# croky_b_1_6_maxi.net
KiCad netlist of a schematic drawn in EAGLE
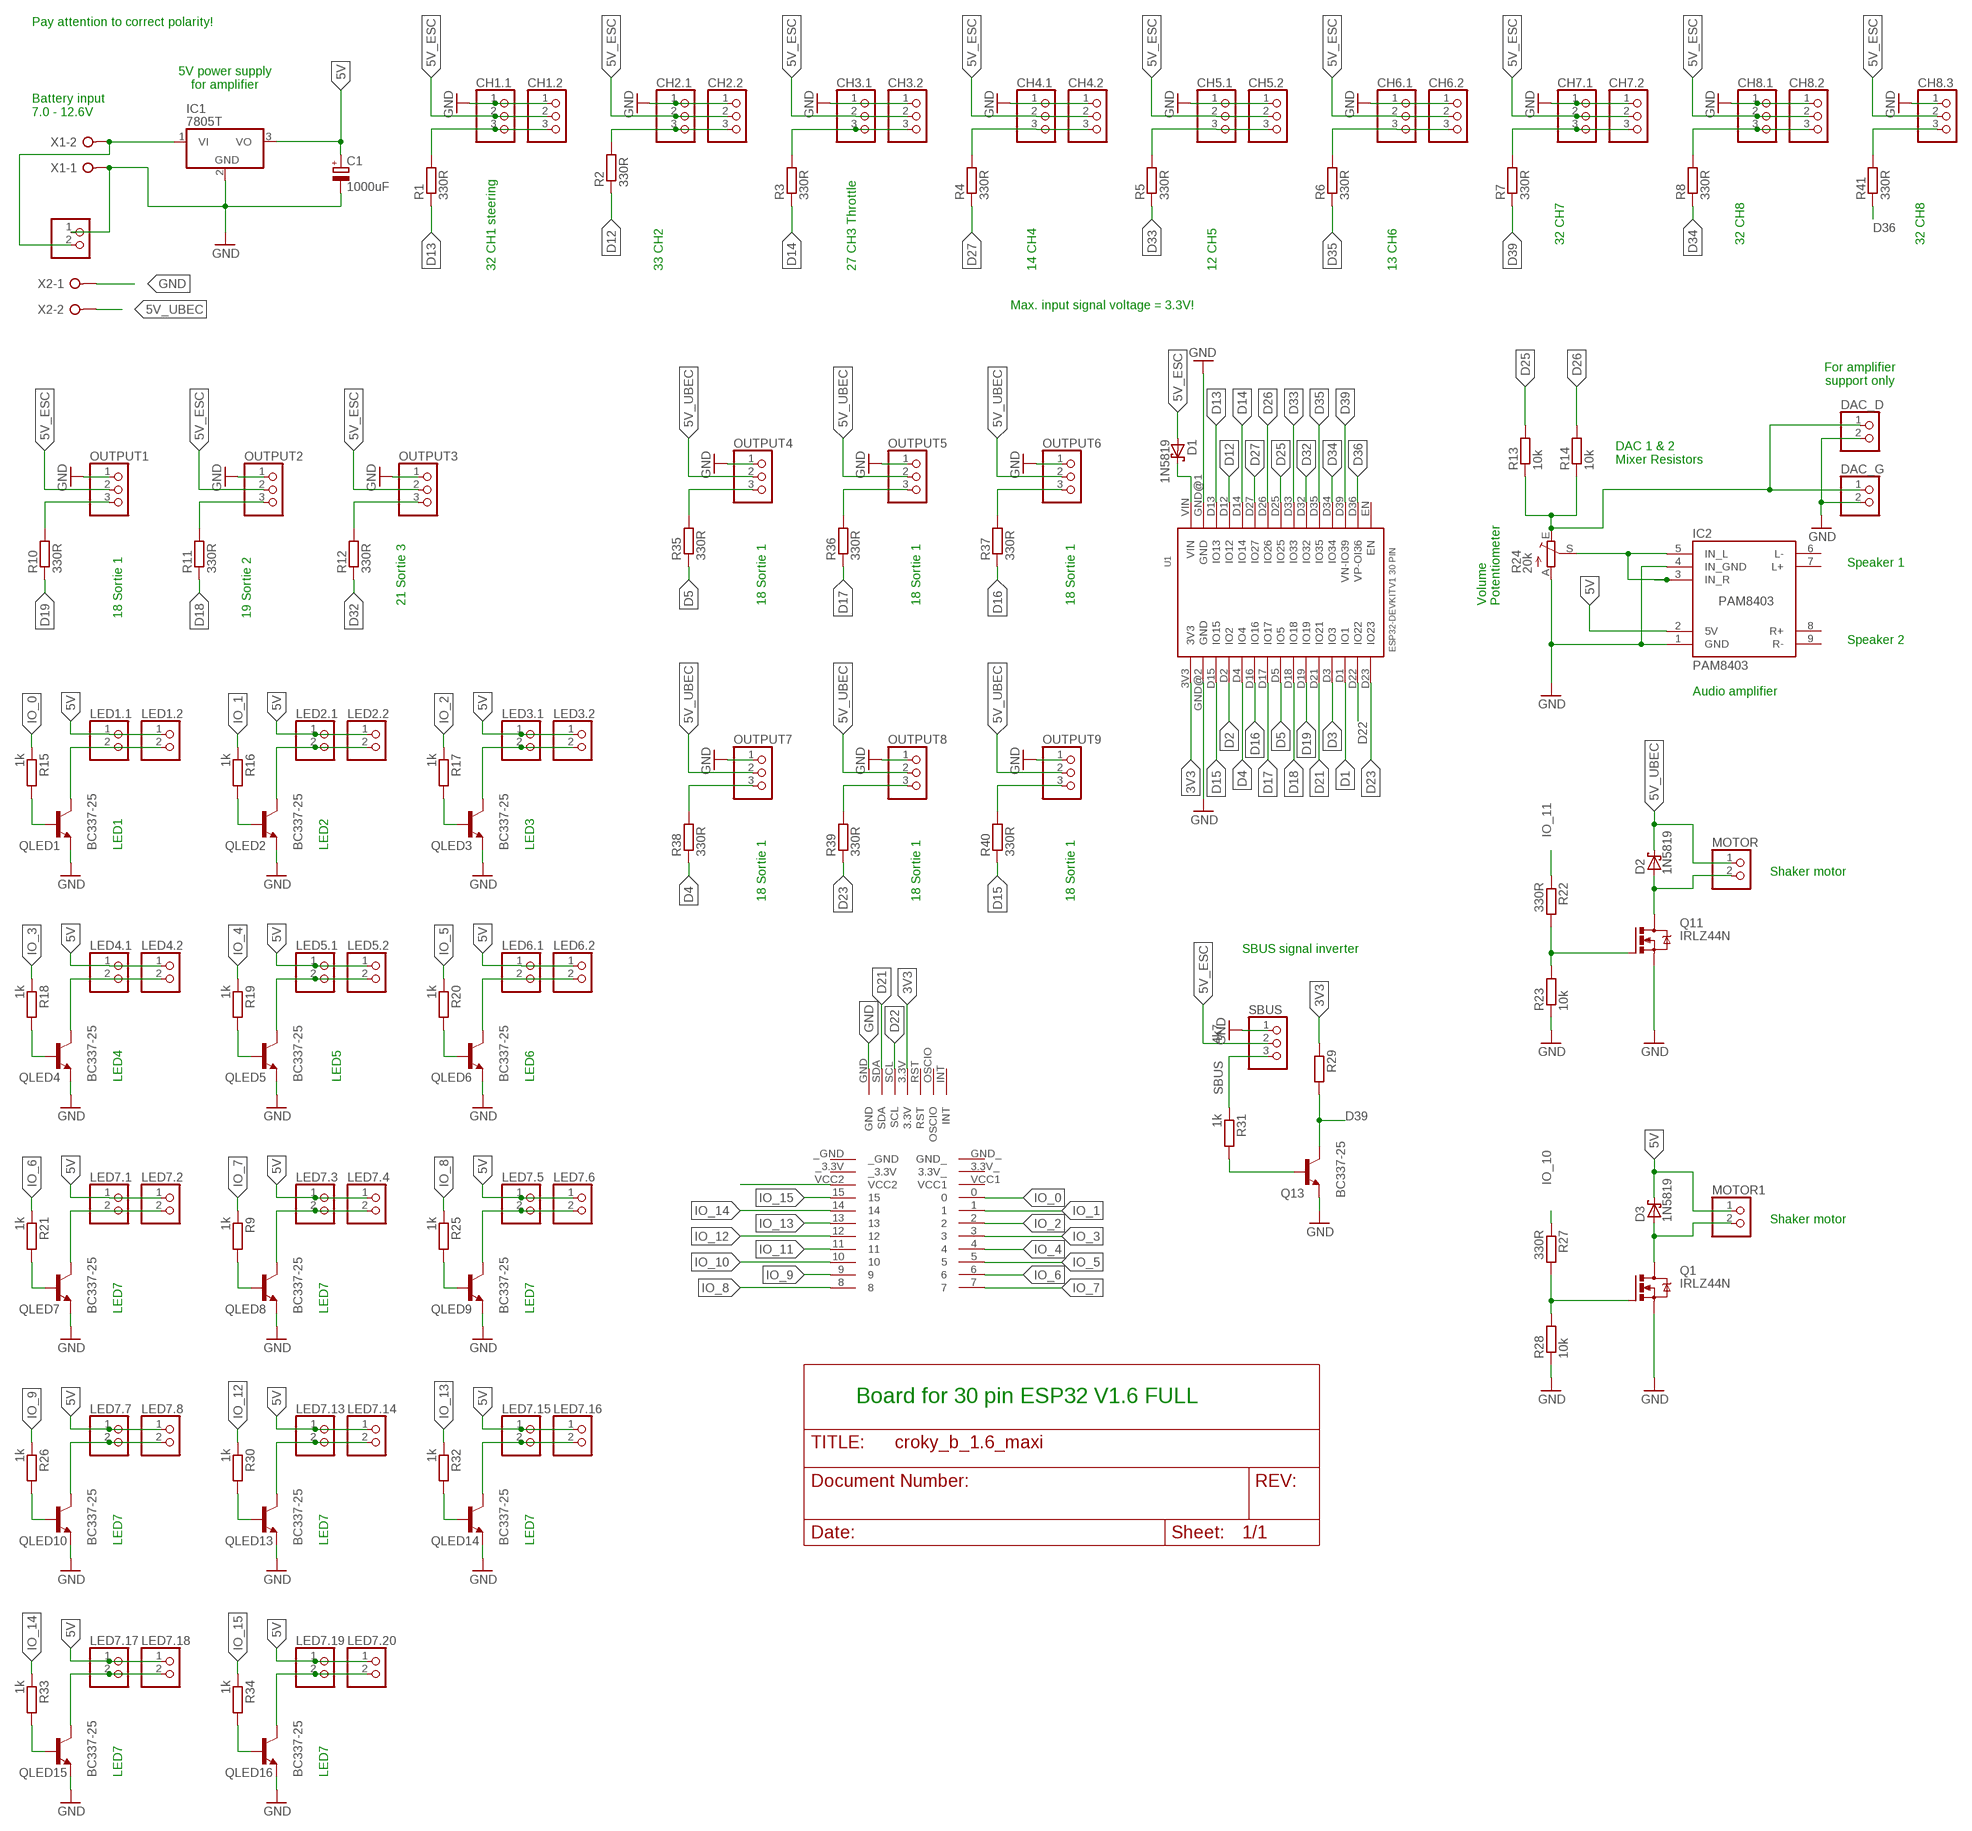
[diagram p0: schematic, sheet 1]

(export (version "E")
  (design (tool "Eeschema 10.0.6"))
  (components
    (comp (ref "C1")
      (value "1000uF")
      (footprint "eagle-import:E5-10,5")
      (libsource (lib "eagle-import") (part "CPOL-EUE5-10.5"))
    )
    (comp (ref "CH1.1")
      (value "PINHD-1X3")
      (footprint "eagle-import:1X03")
      (libsource (lib "eagle-import") (part "PINHD-1X3"))
    )
    (comp (ref "CH1.2")
      (value "PINHD-1X3")
      (footprint "eagle-import:1X03")
      (libsource (lib "eagle-import") (part "PINHD-1X3"))
    )
    (comp (ref "CH2.1")
      (value "PINHD-1X3")
      (footprint "eagle-import:1X03")
      (libsource (lib "eagle-import") (part "PINHD-1X3"))
    )
    (comp (ref "CH2.2")
      (value "PINHD-1X3")
      (footprint "eagle-import:1X03")
      (libsource (lib "eagle-import") (part "PINHD-1X3"))
    )
    (comp (ref "CH3.1")
      (value "PINHD-1X3")
      (footprint "eagle-import:1X03")
      (libsource (lib "eagle-import") (part "PINHD-1X3"))
    )
    (comp (ref "CH3.2")
      (value "PINHD-1X3")
      (footprint "eagle-import:1X03")
      (libsource (lib "eagle-import") (part "PINHD-1X3"))
    )
    (comp (ref "CH4.1")
      (value "PINHD-1X3")
      (footprint "eagle-import:1X03")
      (libsource (lib "eagle-import") (part "PINHD-1X3"))
    )
    (comp (ref "CH4.2")
      (value "PINHD-1X3")
      (footprint "eagle-import:1X03")
      (libsource (lib "eagle-import") (part "PINHD-1X3"))
    )
    (comp (ref "CH5.1")
      (value "PINHD-1X3")
      (footprint "eagle-import:1X03")
      (libsource (lib "eagle-import") (part "PINHD-1X3"))
    )
    (comp (ref "CH5.2")
      (value "PINHD-1X3")
      (footprint "eagle-import:1X03")
      (libsource (lib "eagle-import") (part "PINHD-1X3"))
    )
    (comp (ref "CH6.1")
      (value "PINHD-1X3")
      (footprint "eagle-import:1X03")
      (libsource (lib "eagle-import") (part "PINHD-1X3"))
    )
    (comp (ref "CH6.2")
      (value "PINHD-1X3")
      (footprint "eagle-import:1X03")
      (libsource (lib "eagle-import") (part "PINHD-1X3"))
    )
    (comp (ref "CH7.1")
      (value "PINHD-1X3")
      (footprint "eagle-import:1X03")
      (libsource (lib "eagle-import") (part "PINHD-1X3"))
    )
    (comp (ref "CH7.2")
      (value "PINHD-1X3")
      (footprint "eagle-import:1X03")
      (libsource (lib "eagle-import") (part "PINHD-1X3"))
    )
    (comp (ref "CH8.1")
      (value "PINHD-1X3")
      (footprint "eagle-import:1X03")
      (libsource (lib "eagle-import") (part "PINHD-1X3"))
    )
    (comp (ref "CH8.2")
      (value "PINHD-1X3")
      (footprint "eagle-import:1X03")
      (libsource (lib "eagle-import") (part "PINHD-1X3"))
    )
    (comp (ref "CH8.3")
      (value "PINHD-1X3")
      (footprint "eagle-import:1X03")
      (libsource (lib "eagle-import") (part "PINHD-1X3"))
    )
    (comp (ref "D1")
      (value "1N5819")
      (footprint "eagle-import:DO35-7")
      (libsource (lib "eagle-import") (part "SCHOTTKY-DIODEDO35-7"))
    )
    (comp (ref "D2")
      (value "1N5819")
      (footprint "eagle-import:DO35-7")
      (libsource (lib "eagle-import") (part "SCHOTTKY-DIODEDO35-7"))
    )
    (comp (ref "D3")
      (value "1N5819")
      (footprint "eagle-import:DO35-7")
      (libsource (lib "eagle-import") (part "SCHOTTKY-DIODEDO35-7"))
    )
    (comp (ref "DAC_D")
      (value "PINHD-1X2")
      (footprint "eagle-import:1X02")
      (libsource (lib "eagle-import") (part "PINHD-1X2"))
    )
    (comp (ref "DAC_G")
      (value "PINHD-1X2")
      (footprint "eagle-import:1X02")
      (libsource (lib "eagle-import") (part "PINHD-1X2"))
    )
    (comp (ref "IC1")
      (value "7805T")
      (footprint "eagle-import:TO220H")
      (libsource (lib "eagle-import") (part "78T05"))
    )
    (comp (ref "IC2")
      (value "PAM8403")
      (footprint "eagle-import:PAM8403")
      (libsource (lib "eagle-import") (part "PAM8403"))
    )
    (comp (ref "LED1.1")
      (value "PINHD-1X2")
      (footprint "eagle-import:1X02")
      (libsource (lib "eagle-import") (part "PINHD-1X2"))
    )
    (comp (ref "LED1.2")
      (value "PINHD-1X2")
      (footprint "eagle-import:1X02")
      (libsource (lib "eagle-import") (part "PINHD-1X2"))
    )
    (comp (ref "LED2.1")
      (value "PINHD-1X2")
      (footprint "eagle-import:1X02")
      (libsource (lib "eagle-import") (part "PINHD-1X2"))
    )
    (comp (ref "LED2.2")
      (value "PINHD-1X2")
      (footprint "eagle-import:1X02")
      (libsource (lib "eagle-import") (part "PINHD-1X2"))
    )
    (comp (ref "LED3.1")
      (value "PINHD-1X2")
      (footprint "eagle-import:1X02")
      (libsource (lib "eagle-import") (part "PINHD-1X2"))
    )
    (comp (ref "LED3.2")
      (value "PINHD-1X2")
      (footprint "eagle-import:1X02")
      (libsource (lib "eagle-import") (part "PINHD-1X2"))
    )
    (comp (ref "LED4.1")
      (value "PINHD-1X2")
      (footprint "eagle-import:1X02")
      (libsource (lib "eagle-import") (part "PINHD-1X2"))
    )
    (comp (ref "LED4.2")
      (value "PINHD-1X2")
      (footprint "eagle-import:1X02")
      (libsource (lib "eagle-import") (part "PINHD-1X2"))
    )
    (comp (ref "LED5.1")
      (value "PINHD-1X2")
      (footprint "eagle-import:1X02")
      (libsource (lib "eagle-import") (part "PINHD-1X2"))
    )
    (comp (ref "LED5.2")
      (value "PINHD-1X2")
      (footprint "eagle-import:1X02")
      (libsource (lib "eagle-import") (part "PINHD-1X2"))
    )
    (comp (ref "LED6.1")
      (value "PINHD-1X2")
      (footprint "eagle-import:1X02")
      (libsource (lib "eagle-import") (part "PINHD-1X2"))
    )
    (comp (ref "LED6.2")
      (value "PINHD-1X2")
      (footprint "eagle-import:1X02")
      (libsource (lib "eagle-import") (part "PINHD-1X2"))
    )
    (comp (ref "LED7.1")
      (value "PINHD-1X2")
      (footprint "eagle-import:1X02")
      (libsource (lib "eagle-import") (part "PINHD-1X2"))
    )
    (comp (ref "LED7.2")
      (value "PINHD-1X2")
      (footprint "eagle-import:1X02")
      (libsource (lib "eagle-import") (part "PINHD-1X2"))
    )
    (comp (ref "LED7.3")
      (value "PINHD-1X2")
      (footprint "eagle-import:1X02")
      (libsource (lib "eagle-import") (part "PINHD-1X2"))
    )
    (comp (ref "LED7.4")
      (value "PINHD-1X2")
      (footprint "eagle-import:1X02")
      (libsource (lib "eagle-import") (part "PINHD-1X2"))
    )
    (comp (ref "LED7.5")
      (value "PINHD-1X2")
      (footprint "eagle-import:1X02")
      (libsource (lib "eagle-import") (part "PINHD-1X2"))
    )
    (comp (ref "LED7.6")
      (value "PINHD-1X2")
      (footprint "eagle-import:1X02")
      (libsource (lib "eagle-import") (part "PINHD-1X2"))
    )
    (comp (ref "LED7.7")
      (value "PINHD-1X2")
      (footprint "eagle-import:1X02")
      (libsource (lib "eagle-import") (part "PINHD-1X2"))
    )
    (comp (ref "LED7.8")
      (value "PINHD-1X2")
      (footprint "eagle-import:1X02")
      (libsource (lib "eagle-import") (part "PINHD-1X2"))
    )
    (comp (ref "LED7.13")
      (value "PINHD-1X2")
      (footprint "eagle-import:1X02")
      (libsource (lib "eagle-import") (part "PINHD-1X2"))
    )
    (comp (ref "LED7.14")
      (value "PINHD-1X2")
      (footprint "eagle-import:1X02")
      (libsource (lib "eagle-import") (part "PINHD-1X2"))
    )
    (comp (ref "LED7.15")
      (value "PINHD-1X2")
      (footprint "eagle-import:1X02")
      (libsource (lib "eagle-import") (part "PINHD-1X2"))
    )
    (comp (ref "LED7.16")
      (value "PINHD-1X2")
      (footprint "eagle-import:1X02")
      (libsource (lib "eagle-import") (part "PINHD-1X2"))
    )
    (comp (ref "LED7.17")
      (value "PINHD-1X2")
      (footprint "eagle-import:1X02")
      (libsource (lib "eagle-import") (part "PINHD-1X2"))
    )
    (comp (ref "LED7.18")
      (value "PINHD-1X2")
      (footprint "eagle-import:1X02")
      (libsource (lib "eagle-import") (part "PINHD-1X2"))
    )
    (comp (ref "LED7.19")
      (value "PINHD-1X2")
      (footprint "eagle-import:1X02")
      (libsource (lib "eagle-import") (part "PINHD-1X2"))
    )
    (comp (ref "LED7.20")
      (value "PINHD-1X2")
      (footprint "eagle-import:1X02")
      (libsource (lib "eagle-import") (part "PINHD-1X2"))
    )
    (comp (ref "MOTOR")
      (value "PINHD-1X2")
      (footprint "eagle-import:1X02")
      (libsource (lib "eagle-import") (part "PINHD-1X2"))
    )
    (comp (ref "MOTOR1")
      (value "PINHD-1X2")
      (footprint "eagle-import:1X02")
      (libsource (lib "eagle-import") (part "PINHD-1X2"))
    )
    (comp (ref "MOTOR2")
      (value "PINHD-1X2")
      (footprint "eagle-import:1X02")
      (libsource (lib "eagle-import") (part "PINHD-1X2"))
    )
    (comp (ref "OUTPUT1")
      (value "PINHD-1X3")
      (footprint "eagle-import:1X03")
      (libsource (lib "eagle-import") (part "PINHD-1X3"))
    )
    (comp (ref "OUTPUT2")
      (value "PINHD-1X3")
      (footprint "eagle-import:1X03")
      (libsource (lib "eagle-import") (part "PINHD-1X3"))
    )
    (comp (ref "OUTPUT3")
      (value "PINHD-1X3")
      (footprint "eagle-import:1X03")
      (libsource (lib "eagle-import") (part "PINHD-1X3"))
    )
    (comp (ref "OUTPUT4")
      (value "PINHD-1X3")
      (footprint "eagle-import:1X03")
      (libsource (lib "eagle-import") (part "PINHD-1X3"))
    )
    (comp (ref "OUTPUT5")
      (value "PINHD-1X3")
      (footprint "eagle-import:1X03")
      (libsource (lib "eagle-import") (part "PINHD-1X3"))
    )
    (comp (ref "OUTPUT6")
      (value "PINHD-1X3")
      (footprint "eagle-import:1X03")
      (libsource (lib "eagle-import") (part "PINHD-1X3"))
    )
    (comp (ref "OUTPUT7")
      (value "PINHD-1X3")
      (footprint "eagle-import:1X03")
      (libsource (lib "eagle-import") (part "PINHD-1X3"))
    )
    (comp (ref "OUTPUT8")
      (value "PINHD-1X3")
      (footprint "eagle-import:1X03")
      (libsource (lib "eagle-import") (part "PINHD-1X3"))
    )
    (comp (ref "OUTPUT9")
      (value "PINHD-1X3")
      (footprint "eagle-import:1X03")
      (libsource (lib "eagle-import") (part "PINHD-1X3"))
    )
    (comp (ref "Q1")
      (value "IRLZ44N")
      (footprint "eagle-import:TO220BV")
      (libsource (lib "eagle-import") (part "IRF540"))
    )
    (comp (ref "Q11")
      (value "IRLZ44N")
      (footprint "eagle-import:TO220BV")
      (libsource (lib "eagle-import") (part "IRF540"))
    )
    (comp (ref "Q13")
      (value "BC337-25")
      (footprint "eagle-import:TO92")
      (libsource (lib "eagle-import") (part "BC337-25"))
    )
    (comp (ref "QLED1")
      (value "BC337-25")
      (footprint "eagle-import:TO92")
      (libsource (lib "eagle-import") (part "BC337-25"))
    )
    (comp (ref "QLED2")
      (value "BC337-25")
      (footprint "eagle-import:TO92")
      (libsource (lib "eagle-import") (part "BC337-25"))
    )
    (comp (ref "QLED3")
      (value "BC337-25")
      (footprint "eagle-import:TO92")
      (libsource (lib "eagle-import") (part "BC337-25"))
    )
    (comp (ref "QLED4")
      (value "BC337-25")
      (footprint "eagle-import:TO92")
      (libsource (lib "eagle-import") (part "BC337-25"))
    )
    (comp (ref "QLED5")
      (value "BC337-25")
      (footprint "eagle-import:TO92")
      (libsource (lib "eagle-import") (part "BC337-25"))
    )
    (comp (ref "QLED6")
      (value "BC337-25")
      (footprint "eagle-import:TO92")
      (libsource (lib "eagle-import") (part "BC337-25"))
    )
    (comp (ref "QLED7")
      (value "BC337-25")
      (footprint "eagle-import:TO92")
      (libsource (lib "eagle-import") (part "BC337-25"))
    )
    (comp (ref "QLED8")
      (value "BC337-25")
      (footprint "eagle-import:TO92")
      (libsource (lib "eagle-import") (part "BC337-25"))
    )
    (comp (ref "QLED9")
      (value "BC337-25")
      (footprint "eagle-import:TO92")
      (libsource (lib "eagle-import") (part "BC337-25"))
    )
    (comp (ref "QLED10")
      (value "BC337-25")
      (footprint "eagle-import:TO92")
      (libsource (lib "eagle-import") (part "BC337-25"))
    )
    (comp (ref "QLED13")
      (value "BC337-25")
      (footprint "eagle-import:TO92")
      (libsource (lib "eagle-import") (part "BC337-25"))
    )
    (comp (ref "QLED14")
      (value "BC337-25")
      (footprint "eagle-import:TO92")
      (libsource (lib "eagle-import") (part "BC337-25"))
    )
    (comp (ref "QLED15")
      (value "BC337-25")
      (footprint "eagle-import:TO92")
      (libsource (lib "eagle-import") (part "BC337-25"))
    )
    (comp (ref "QLED16")
      (value "BC337-25")
      (footprint "eagle-import:TO92")
      (libsource (lib "eagle-import") (part "BC337-25"))
    )
    (comp (ref "R1")
      (value "330R")
      (footprint "eagle-import:0207_2V")
      (libsource (lib "eagle-import") (part "R-EU_0207/2V"))
    )
    (comp (ref "R2")
      (value "330R")
      (footprint "eagle-import:0207_2V")
      (libsource (lib "eagle-import") (part "R-EU_0207/2V"))
    )
    (comp (ref "R3")
      (value "330R")
      (footprint "eagle-import:0207_2V")
      (fields (field (name "SPICEPREFIX") "R"))
      (libsource (lib "eagle-import") (part "R-EU_0207/2V"))
    )
    (comp (ref "R4")
      (value "330R")
      (footprint "eagle-import:0207_2V")
      (libsource (lib "eagle-import") (part "R-EU_0207/2V"))
    )
    (comp (ref "R5")
      (value "330R")
      (footprint "eagle-import:0207_2V")
      (libsource (lib "eagle-import") (part "R-EU_0207/2V"))
    )
    (comp (ref "R6")
      (value "330R")
      (footprint "eagle-import:0207_2V")
      (libsource (lib "eagle-import") (part "R-EU_0207/2V"))
    )
    (comp (ref "R7")
      (value "330R")
      (footprint "eagle-import:0207_2V")
      (libsource (lib "eagle-import") (part "R-EU_0207/2V"))
    )
    (comp (ref "R8")
      (value "330R")
      (footprint "eagle-import:0207_2V")
      (libsource (lib "eagle-import") (part "R-EU_0207/2V"))
    )
    (comp (ref "R9")
      (value "1k")
      (footprint "eagle-import:0207_2V")
      (libsource (lib "eagle-import") (part "R-EU_0207/2V"))
    )
    (comp (ref "R10")
      (value "330R")
      (footprint "eagle-import:0207_2V")
      (libsource (lib "eagle-import") (part "R-EU_0207/2V"))
    )
    (comp (ref "R11")
      (value "330R")
      (footprint "eagle-import:0207_2V")
      (libsource (lib "eagle-import") (part "R-EU_0207/2V"))
    )
    (comp (ref "R12")
      (value "330R")
      (footprint "eagle-import:0207_2V")
      (libsource (lib "eagle-import") (part "R-EU_0207/2V"))
    )
    (comp (ref "R13")
      (value "10k")
      (footprint "eagle-import:0207_10")
      (libsource (lib "eagle-import") (part "R-EU_0207/10"))
    )
    (comp (ref "R14")
      (value "10k")
      (footprint "eagle-import:0207_10")
      (libsource (lib "eagle-import") (part "R-EU_0207/10"))
    )
    (comp (ref "R15")
      (value "1k")
      (footprint "eagle-import:0207_2V")
      (libsource (lib "eagle-import") (part "R-EU_0207/2V"))
    )
    (comp (ref "R16")
      (value "1k")
      (footprint "eagle-import:0207_2V")
      (libsource (lib "eagle-import") (part "R-EU_0207/2V"))
    )
    (comp (ref "R17")
      (value "1k")
      (footprint "eagle-import:0207_2V")
      (libsource (lib "eagle-import") (part "R-EU_0207/2V"))
    )
    (comp (ref "R18")
      (value "1k")
      (footprint "eagle-import:0207_2V")
      (libsource (lib "eagle-import") (part "R-EU_0207/2V"))
    )
    (comp (ref "R19")
      (value "1k")
      (footprint "eagle-import:0207_2V")
      (libsource (lib "eagle-import") (part "R-EU_0207/2V"))
    )
    (comp (ref "R20")
      (value "1k")
      (footprint "eagle-import:0207_2V")
      (libsource (lib "eagle-import") (part "R-EU_0207/2V"))
    )
    (comp (ref "R21")
      (value "1k")
      (footprint "eagle-import:0207_2V")
      (libsource (lib "eagle-import") (part "R-EU_0207/2V"))
    )
    (comp (ref "R22")
      (value "330R")
      (footprint "eagle-import:0207_2V")
      (libsource (lib "eagle-import") (part "R-EU_0207/2V"))
    )
    (comp (ref "R23")
      (value "10k")
      (footprint "eagle-import:0207_2V")
      (libsource (lib "eagle-import") (part "R-EU_0207/2V"))
    )
    (comp (ref "R24")
      (value "20k")
      (footprint "eagle-import:S64W")
      (libsource (lib "eagle-import") (part "TRIM_EU-S64W"))
    )
    (comp (ref "R25")
      (value "1k")
      (footprint "eagle-import:0207_2V")
      (libsource (lib "eagle-import") (part "R-EU_0207/2V"))
    )
    (comp (ref "R26")
      (value "1k")
      (footprint "eagle-import:0207_2V")
      (libsource (lib "eagle-import") (part "R-EU_0207/2V"))
    )
    (comp (ref "R27")
      (value "330R")
      (footprint "eagle-import:0207_2V")
      (libsource (lib "eagle-import") (part "R-EU_0207/2V"))
    )
    (comp (ref "R28")
      (value "10k")
      (footprint "eagle-import:0207_2V")
      (libsource (lib "eagle-import") (part "R-EU_0207/2V"))
    )
    (comp (ref "R29")
      (value "4k7")
      (footprint "eagle-import:0207_2V")
      (libsource (lib "eagle-import") (part "R-EU_0207/2V"))
    )
    (comp (ref "R30")
      (value "1k")
      (footprint "eagle-import:0207_2V")
      (libsource (lib "eagle-import") (part "R-EU_0207/2V"))
    )
    (comp (ref "R31")
      (value "1k")
      (footprint "eagle-import:0207_2V")
      (libsource (lib "eagle-import") (part "R-EU_0207/2V"))
    )
    (comp (ref "R32")
      (value "1k")
      (footprint "eagle-import:0207_2V")
      (libsource (lib "eagle-import") (part "R-EU_0207/2V"))
    )
    (comp (ref "R33")
      (value "1k")
      (footprint "eagle-import:0207_2V")
      (libsource (lib "eagle-import") (part "R-EU_0207/2V"))
    )
    (comp (ref "R34")
      (value "1k")
      (footprint "eagle-import:0207_2V")
      (libsource (lib "eagle-import") (part "R-EU_0207/2V"))
    )
    (comp (ref "R35")
      (value "330R")
      (footprint "eagle-import:0207_2V")
      (libsource (lib "eagle-import") (part "R-EU_0207/2V"))
    )
    (comp (ref "R36")
      (value "330R")
      (footprint "eagle-import:0207_2V")
      (libsource (lib "eagle-import") (part "R-EU_0207/2V"))
    )
    (comp (ref "R37")
      (value "330R")
      (footprint "eagle-import:0207_2V")
      (libsource (lib "eagle-import") (part "R-EU_0207/2V"))
    )
    (comp (ref "R38")
      (value "330R")
      (footprint "eagle-import:0207_2V")
      (libsource (lib "eagle-import") (part "R-EU_0207/2V"))
    )
    (comp (ref "R39")
      (value "330R")
      (footprint "eagle-import:0207_2V")
      (libsource (lib "eagle-import") (part "R-EU_0207/2V"))
    )
    (comp (ref "R40")
      (value "330R")
      (footprint "eagle-import:0207_2V")
      (libsource (lib "eagle-import") (part "R-EU_0207/2V"))
    )
    (comp (ref "R41")
      (value "330R")
      (footprint "eagle-import:0207_2V")
      (libsource (lib "eagle-import") (part "R-EU_0207/2V"))
    )
    (comp (ref "SBUS")
      (value "PINHD-1X3")
      (footprint "eagle-import:1X03")
      (libsource (lib "eagle-import") (part "PINHD-1X3"))
    )
    (comp (ref "U$1")
      (value "TEST")
      (footprint "eagle-import:TEST")
      (libsource (lib "eagle-import") (part "TEST"))
    )
    (comp (ref "U1")
      (value "ESP32DEVKITV1")
      (footprint "eagle-import:ESP32-DEVKITV1")
      (libsource (lib "eagle-import") (part "ESP32DEVKITV1"))
    )
    (comp (ref "X1")
      (value "W237-02P")
      (footprint "eagle-import:W237-132")
      (libsource (lib "eagle-import") (part "W237-02P"))
    )
    (comp (ref "X2")
      (value "W237-02P")
      (footprint "eagle-import:W237-132")
      (libsource (lib "eagle-import") (part "W237-02P"))
    )
  )
  (nets
    (net (code "1") (name "/SBUS") (class "Default")
      (node (ref "R31") (pin "1") (pinfunction "1_1") (pintype "passive"))
      (node (ref "SBUS") (pin "3") (pinfunction "3_3") (pintype "passive"))
    )
    (net (code "2") (name "3V3") (class "Default")
      (node (ref "R29") (pin "1") (pinfunction "1_1") (pintype "passive"))
      (node (ref "U$1") (pin "3.3V") (pinfunction "3.3V_3.3V") (pintype "bidirectional"))
      (node (ref "U1") (pin "3V3") (pinfunction "3V3_3V3") (pintype "bidirectional"))
    )
    (net (code "3") (name "5V") (class "Default")
      (node (ref "C1") (pin "+") (pinfunction "+_+") (pintype "passive"))
      (node (ref "D3") (pin "C") (pinfunction "C_C") (pintype "passive"))
      (node (ref "IC1") (pin "3") (pinfunction "VO_3") (pintype "passive"))
      (node (ref "IC2") (pin "2") (pinfunction "5V_2") (pintype "input"))
      (node (ref "LED1.1") (pin "1") (pinfunction "1_1") (pintype "passive"))
      (node (ref "LED1.2") (pin "1") (pinfunction "1_1") (pintype "passive"))
      (node (ref "LED2.1") (pin "1") (pinfunction "1_1") (pintype "passive"))
      (node (ref "LED2.2") (pin "1") (pinfunction "1_1") (pintype "passive"))
      (node (ref "LED3.1") (pin "1") (pinfunction "1_1") (pintype "passive"))
      (node (ref "LED3.2") (pin "1") (pinfunction "1_1") (pintype "passive"))
      (node (ref "LED4.1") (pin "1") (pinfunction "1_1") (pintype "passive"))
      (node (ref "LED4.2") (pin "1") (pinfunction "1_1") (pintype "passive"))
      (node (ref "LED5.1") (pin "1") (pinfunction "1_1") (pintype "passive"))
      (node (ref "LED5.2") (pin "1") (pinfunction "1_1") (pintype "passive"))
      (node (ref "LED6.1") (pin "1") (pinfunction "1_1") (pintype "passive"))
      (node (ref "LED6.2") (pin "1") (pinfunction "1_1") (pintype "passive"))
      (node (ref "LED7.1") (pin "1") (pinfunction "1_1") (pintype "passive"))
      (node (ref "LED7.13") (pin "1") (pinfunction "1_1") (pintype "passive"))
      (node (ref "LED7.14") (pin "1") (pinfunction "1_1") (pintype "passive"))
      (node (ref "LED7.15") (pin "1") (pinfunction "1_1") (pintype "passive"))
      (node (ref "LED7.16") (pin "1") (pinfunction "1_1") (pintype "passive"))
      (node (ref "LED7.17") (pin "1") (pinfunction "1_1") (pintype "passive"))
      (node (ref "LED7.18") (pin "1") (pinfunction "1_1") (pintype "passive"))
      (node (ref "LED7.19") (pin "1") (pinfunction "1_1") (pintype "passive"))
      (node (ref "LED7.2") (pin "1") (pinfunction "1_1") (pintype "passive"))
      (node (ref "LED7.20") (pin "1") (pinfunction "1_1") (pintype "passive"))
      (node (ref "LED7.3") (pin "1") (pinfunction "1_1") (pintype "passive"))
      (node (ref "LED7.4") (pin "1") (pinfunction "1_1") (pintype "passive"))
      (node (ref "LED7.5") (pin "1") (pinfunction "1_1") (pintype "passive"))
      (node (ref "LED7.6") (pin "1") (pinfunction "1_1") (pintype "passive"))
      (node (ref "LED7.7") (pin "1") (pinfunction "1_1") (pintype "passive"))
      (node (ref "LED7.8") (pin "1") (pinfunction "1_1") (pintype "passive"))
      (node (ref "MOTOR1") (pin "1") (pinfunction "1_1") (pintype "passive"))
    )
    (net (code "4") (name "5V_ESC") (class "Default")
      (node (ref "CH1.1") (pin "2") (pinfunction "2_2") (pintype "passive"))
      (node (ref "CH1.2") (pin "2") (pinfunction "2_2") (pintype "passive"))
      (node (ref "CH2.1") (pin "2") (pinfunction "2_2") (pintype "passive"))
      (node (ref "CH2.2") (pin "2") (pinfunction "2_2") (pintype "passive"))
      (node (ref "CH3.1") (pin "2") (pinfunction "2_2") (pintype "passive"))
      (node (ref "CH3.2") (pin "2") (pinfunction "2_2") (pintype "passive"))
      (node (ref "CH4.1") (pin "2") (pinfunction "2_2") (pintype "passive"))
      (node (ref "CH4.2") (pin "2") (pinfunction "2_2") (pintype "passive"))
      (node (ref "CH5.1") (pin "2") (pinfunction "2_2") (pintype "passive"))
      (node (ref "CH5.2") (pin "2") (pinfunction "2_2") (pintype "passive"))
      (node (ref "CH6.1") (pin "2") (pinfunction "2_2") (pintype "passive"))
      (node (ref "CH6.2") (pin "2") (pinfunction "2_2") (pintype "passive"))
      (node (ref "CH7.1") (pin "2") (pinfunction "2_2") (pintype "passive"))
      (node (ref "CH7.2") (pin "2") (pinfunction "2_2") (pintype "passive"))
      (node (ref "CH8.1") (pin "2") (pinfunction "2_2") (pintype "passive"))
      (node (ref "CH8.2") (pin "2") (pinfunction "2_2") (pintype "passive"))
      (node (ref "CH8.3") (pin "2") (pinfunction "2_2") (pintype "passive"))
      (node (ref "D1") (pin "A") (pinfunction "A_A") (pintype "passive"))
      (node (ref "OUTPUT1") (pin "2") (pinfunction "2_2") (pintype "passive"))
      (node (ref "OUTPUT2") (pin "2") (pinfunction "2_2") (pintype "passive"))
      (node (ref "OUTPUT3") (pin "2") (pinfunction "2_2") (pintype "passive"))
      (node (ref "SBUS") (pin "2") (pinfunction "2_2") (pintype "passive"))
    )
    (net (code "5") (name "5V_UBEC") (class "Default")
      (node (ref "D2") (pin "C") (pinfunction "C_C") (pintype "passive"))
      (node (ref "MOTOR") (pin "1") (pinfunction "1_1") (pintype "passive"))
      (node (ref "OUTPUT4") (pin "2") (pinfunction "2_2") (pintype "passive"))
      (node (ref "OUTPUT5") (pin "2") (pinfunction "2_2") (pintype "passive"))
      (node (ref "OUTPUT6") (pin "2") (pinfunction "2_2") (pintype "passive"))
      (node (ref "OUTPUT7") (pin "2") (pinfunction "2_2") (pintype "passive"))
      (node (ref "OUTPUT8") (pin "2") (pinfunction "2_2") (pintype "passive"))
      (node (ref "OUTPUT9") (pin "2") (pinfunction "2_2") (pintype "passive"))
      (node (ref "X2") (pin "2") (pinfunction "KL_2") (pintype "passive"))
    )
    (net (code "6") (name "D1") (class "Default")
      (node (ref "U1") (pin "D1") (pinfunction "IO1_D1") (pintype "bidirectional"))
    )
    (net (code "7") (name "D2") (class "Default")
      (node (ref "U1") (pin "D2") (pinfunction "IO2_D2") (pintype "bidirectional"))
    )
    (net (code "8") (name "D3") (class "Default")
      (node (ref "U1") (pin "D3") (pinfunction "IO3_D3") (pintype "bidirectional"))
    )
    (net (code "9") (name "D4") (class "Default")
      (node (ref "R38") (pin "1") (pinfunction "1_1") (pintype "passive"))
      (node (ref "U1") (pin "D4") (pinfunction "IO4_D4") (pintype "bidirectional"))
    )
    (net (code "10") (name "D5") (class "Default")
      (node (ref "R35") (pin "1") (pinfunction "1_1") (pintype "passive"))
      (node (ref "U1") (pin "D5") (pinfunction "IO5_D5") (pintype "bidirectional"))
    )
    (net (code "11") (name "D12") (class "Default")
      (node (ref "R2") (pin "1") (pinfunction "1_1") (pintype "passive"))
      (node (ref "U1") (pin "D12") (pinfunction "IO12_D12") (pintype "bidirectional"))
    )
    (net (code "12") (name "D13") (class "Default")
      (node (ref "R1") (pin "1") (pinfunction "1_1") (pintype "passive"))
      (node (ref "U1") (pin "D13") (pinfunction "IO13_D13") (pintype "bidirectional"))
    )
    (net (code "13") (name "D14") (class "Default")
      (node (ref "R3") (pin "1") (pinfunction "1_1") (pintype "passive"))
      (node (ref "U1") (pin "D14") (pinfunction "IO14_D14") (pintype "bidirectional"))
    )
    (net (code "14") (name "D15") (class "Default")
      (node (ref "R40") (pin "1") (pinfunction "1_1") (pintype "passive"))
      (node (ref "U1") (pin "D15") (pinfunction "IO15_D15") (pintype "bidirectional"))
    )
    (net (code "15") (name "D16") (class "Default")
      (node (ref "R37") (pin "1") (pinfunction "1_1") (pintype "passive"))
      (node (ref "U1") (pin "D16") (pinfunction "IO16_D16") (pintype "bidirectional"))
    )
    (net (code "16") (name "D17") (class "Default")
      (node (ref "R36") (pin "1") (pinfunction "1_1") (pintype "passive"))
      (node (ref "U1") (pin "D17") (pinfunction "IO17_D17") (pintype "bidirectional"))
    )
    (net (code "17") (name "D18") (class "Default")
      (node (ref "R11") (pin "1") (pinfunction "1_1") (pintype "passive"))
      (node (ref "U1") (pin "D18") (pinfunction "IO18_D18") (pintype "bidirectional"))
    )
    (net (code "18") (name "D19") (class "Default")
      (node (ref "R10") (pin "1") (pinfunction "1_1") (pintype "passive"))
      (node (ref "U1") (pin "D19") (pinfunction "IO19_D19") (pintype "bidirectional"))
    )
    (net (code "19") (name "D21") (class "Default")
      (node (ref "U$1") (pin "SDA") (pinfunction "SDA_SDA") (pintype "bidirectional"))
      (node (ref "U1") (pin "D21") (pinfunction "IO21_D21") (pintype "bidirectional"))
    )
    (net (code "20") (name "D22") (class "Default")
      (node (ref "U$1") (pin "SCL") (pinfunction "SCL_SCL") (pintype "bidirectional"))
      (node (ref "U1") (pin "D22") (pinfunction "IO22_D22") (pintype "bidirectional"))
    )
    (net (code "21") (name "D23") (class "Default")
      (node (ref "R39") (pin "1") (pinfunction "1_1") (pintype "passive"))
      (node (ref "U1") (pin "D23") (pinfunction "IO23_D23") (pintype "bidirectional"))
    )
    (net (code "22") (name "D25") (class "Default")
      (node (ref "R13") (pin "2") (pinfunction "2_2") (pintype "passive"))
      (node (ref "U1") (pin "D25") (pinfunction "IO25_D25") (pintype "bidirectional"))
    )
    (net (code "23") (name "D26") (class "Default")
      (node (ref "R14") (pin "2") (pinfunction "2_2") (pintype "passive"))
      (node (ref "U1") (pin "D26") (pinfunction "IO26_D26") (pintype "bidirectional"))
    )
    (net (code "24") (name "D27") (class "Default")
      (node (ref "R4") (pin "1") (pinfunction "1_1") (pintype "passive"))
      (node (ref "U1") (pin "D27") (pinfunction "IO27_D27") (pintype "bidirectional"))
    )
    (net (code "25") (name "D32") (class "Default")
      (node (ref "R12") (pin "1") (pinfunction "1_1") (pintype "passive"))
      (node (ref "U1") (pin "D32") (pinfunction "IO32_D32") (pintype "bidirectional"))
    )
    (net (code "26") (name "D33") (class "Default")
      (node (ref "R5") (pin "1") (pinfunction "1_1") (pintype "passive"))
      (node (ref "U1") (pin "D33") (pinfunction "IO33_D33") (pintype "bidirectional"))
    )
    (net (code "27") (name "D34") (class "Default")
      (node (ref "R8") (pin "1") (pinfunction "1_1") (pintype "passive"))
      (node (ref "U1") (pin "D34") (pinfunction "IO34_D34") (pintype "bidirectional"))
    )
    (net (code "28") (name "D35") (class "Default")
      (node (ref "R6") (pin "1") (pinfunction "1_1") (pintype "passive"))
      (node (ref "U1") (pin "D35") (pinfunction "IO35_D35") (pintype "bidirectional"))
    )
    (net (code "29") (name "D36") (class "Default")
      (node (ref "R41") (pin "1") (pinfunction "1_1") (pintype "passive"))
      (node (ref "U1") (pin "D36") (pinfunction "VP-OI36_D36") (pintype "bidirectional"))
    )
    (net (code "30") (name "D39") (class "Default")
      (node (ref "Q13") (pin "3") (pinfunction "C_3") (pintype "passive"))
      (node (ref "R29") (pin "2") (pinfunction "2_2") (pintype "passive"))
      (node (ref "R7") (pin "1") (pinfunction "1_1") (pintype "passive"))
      (node (ref "U1") (pin "D39") (pinfunction "VN-IO39_D39") (pintype "bidirectional"))
    )
    (net (code "31") (name "GND") (class "Default")
      (node (ref "C1") (pin "-") (pinfunction "-_-") (pintype "passive"))
      (node (ref "CH1.1") (pin "1") (pinfunction "1_1") (pintype "passive"))
      (node (ref "CH1.2") (pin "1") (pinfunction "1_1") (pintype "passive"))
      (node (ref "CH2.1") (pin "1") (pinfunction "1_1") (pintype "passive"))
      (node (ref "CH2.2") (pin "1") (pinfunction "1_1") (pintype "passive"))
      (node (ref "CH3.1") (pin "1") (pinfunction "1_1") (pintype "passive"))
      (node (ref "CH3.2") (pin "1") (pinfunction "1_1") (pintype "passive"))
      (node (ref "CH4.1") (pin "1") (pinfunction "1_1") (pintype "passive"))
      (node (ref "CH4.2") (pin "1") (pinfunction "1_1") (pintype "passive"))
      (node (ref "CH5.1") (pin "1") (pinfunction "1_1") (pintype "passive"))
      (node (ref "CH5.2") (pin "1") (pinfunction "1_1") (pintype "passive"))
      (node (ref "CH6.1") (pin "1") (pinfunction "1_1") (pintype "passive"))
      (node (ref "CH6.2") (pin "1") (pinfunction "1_1") (pintype "passive"))
      (node (ref "CH7.1") (pin "1") (pinfunction "1_1") (pintype "passive"))
      (node (ref "CH7.2") (pin "1") (pinfunction "1_1") (pintype "passive"))
      (node (ref "CH8.1") (pin "1") (pinfunction "1_1") (pintype "passive"))
      (node (ref "CH8.2") (pin "1") (pinfunction "1_1") (pintype "passive"))
      (node (ref "CH8.3") (pin "1") (pinfunction "1_1") (pintype "passive"))
      (node (ref "DAC_D") (pin "2") (pinfunction "2_2") (pintype "passive"))
      (node (ref "DAC_G") (pin "2") (pinfunction "2_2") (pintype "passive"))
      (node (ref "IC1") (pin "2") (pinfunction "GND_2") (pintype "passive"))
      (node (ref "IC2") (pin "1") (pinfunction "GND_1") (pintype "input"))
      (node (ref "IC2") (pin "4") (pinfunction "IN_GND_4") (pintype "input"))
      (node (ref "MOTOR2") (pin "1") (pinfunction "1_1") (pintype "passive"))
      (node (ref "OUTPUT1") (pin "1") (pinfunction "1_1") (pintype "passive"))
      (node (ref "OUTPUT2") (pin "1") (pinfunction "1_1") (pintype "passive"))
      (node (ref "OUTPUT3") (pin "1") (pinfunction "1_1") (pintype "passive"))
      (node (ref "OUTPUT4") (pin "1") (pinfunction "1_1") (pintype "passive"))
      (node (ref "OUTPUT5") (pin "1") (pinfunction "1_1") (pintype "passive"))
      (node (ref "OUTPUT6") (pin "1") (pinfunction "1_1") (pintype "passive"))
      (node (ref "OUTPUT7") (pin "1") (pinfunction "1_1") (pintype "passive"))
      (node (ref "OUTPUT8") (pin "1") (pinfunction "1_1") (pintype "passive"))
      (node (ref "OUTPUT9") (pin "1") (pinfunction "1_1") (pintype "passive"))
      (node (ref "Q1") (pin "S") (pinfunction "S_S") (pintype "passive"))
      (node (ref "Q11") (pin "S") (pinfunction "S_S") (pintype "passive"))
      (node (ref "Q13") (pin "1") (pinfunction "E_1") (pintype "passive"))
      (node (ref "QLED1") (pin "1") (pinfunction "E_1") (pintype "passive"))
      (node (ref "QLED10") (pin "1") (pinfunction "E_1") (pintype "passive"))
      (node (ref "QLED13") (pin "1") (pinfunction "E_1") (pintype "passive"))
      (node (ref "QLED14") (pin "1") (pinfunction "E_1") (pintype "passive"))
      (node (ref "QLED15") (pin "1") (pinfunction "E_1") (pintype "passive"))
      (node (ref "QLED16") (pin "1") (pinfunction "E_1") (pintype "passive"))
      (node (ref "QLED2") (pin "1") (pinfunction "E_1") (pintype "passive"))
      (node (ref "QLED3") (pin "1") (pinfunction "E_1") (pintype "passive"))
      (node (ref "QLED4") (pin "1") (pinfunction "E_1") (pintype "passive"))
      (node (ref "QLED5") (pin "1") (pinfunction "E_1") (pintype "passive"))
      (node (ref "QLED6") (pin "1") (pinfunction "E_1") (pintype "passive"))
      (node (ref "QLED7") (pin "1") (pinfunction "E_1") (pintype "passive"))
      (node (ref "QLED8") (pin "1") (pinfunction "E_1") (pintype "passive"))
      (node (ref "QLED9") (pin "1") (pinfunction "E_1") (pintype "passive"))
      (node (ref "R23") (pin "1") (pinfunction "1_1") (pintype "passive"))
      (node (ref "R24") (pin "A") (pinfunction "A_A") (pintype "passive"))
      (node (ref "R28") (pin "1") (pinfunction "1_1") (pintype "passive"))
      (node (ref "SBUS") (pin "1") (pinfunction "1_1") (pintype "passive"))
      (node (ref "U$1") (pin "GND") (pinfunction "GND_GND") (pintype "bidirectional"))
      (node (ref "U1") (pin "GND@1") (pinfunction "GND_GND@1") (pintype "bidirectional"))
      (node (ref "U1") (pin "GND@2") (pinfunction "GND_GND@2") (pintype "bidirectional"))
      (node (ref "X1") (pin "1") (pinfunction "KL_1") (pintype "passive"))
      (node (ref "X2") (pin "1") (pinfunction "KL_1") (pintype "passive"))
    )
    (net (code "32") (name "IO_0") (class "Default")
      (node (ref "R15") (pin "1") (pinfunction "1_1") (pintype "passive"))
      (node (ref "U$1") (pin "0") (pinfunction "0_0") (pintype "bidirectional"))
    )
    (net (code "33") (name "IO_1") (class "Default")
      (node (ref "R16") (pin "1") (pinfunction "1_1") (pintype "passive"))
      (node (ref "U$1") (pin "1") (pinfunction "1_1") (pintype "bidirectional"))
    )
    (net (code "34") (name "IO_2") (class "Default")
      (node (ref "R17") (pin "1") (pinfunction "1_1") (pintype "passive"))
      (node (ref "U$1") (pin "2") (pinfunction "2_2") (pintype "bidirectional"))
    )
    (net (code "35") (name "IO_3") (class "Default")
      (node (ref "R18") (pin "1") (pinfunction "1_1") (pintype "passive"))
      (node (ref "U$1") (pin "3") (pinfunction "3_3") (pintype "bidirectional"))
    )
    (net (code "36") (name "IO_4") (class "Default")
      (node (ref "R19") (pin "1") (pinfunction "1_1") (pintype "passive"))
      (node (ref "U$1") (pin "4") (pinfunction "4_4") (pintype "bidirectional"))
    )
    (net (code "37") (name "IO_5") (class "Default")
      (node (ref "R20") (pin "1") (pinfunction "1_1") (pintype "passive"))
      (node (ref "U$1") (pin "5") (pinfunction "5_5") (pintype "bidirectional"))
    )
    (net (code "38") (name "IO_6") (class "Default")
      (node (ref "R21") (pin "1") (pinfunction "1_1") (pintype "passive"))
      (node (ref "U$1") (pin "6") (pinfunction "6_6") (pintype "bidirectional"))
    )
    (net (code "39") (name "IO_7") (class "Default")
      (node (ref "R9") (pin "1") (pinfunction "1_1") (pintype "passive"))
      (node (ref "U$1") (pin "7") (pinfunction "7_7") (pintype "bidirectional"))
    )
    (net (code "40") (name "IO_8") (class "Default")
      (node (ref "R25") (pin "1") (pinfunction "1_1") (pintype "passive"))
      (node (ref "U$1") (pin "8") (pinfunction "8_8") (pintype "bidirectional"))
    )
    (net (code "41") (name "IO_9") (class "Default")
      (node (ref "R26") (pin "1") (pinfunction "1_1") (pintype "passive"))
      (node (ref "U$1") (pin "9") (pinfunction "9_9") (pintype "bidirectional"))
    )
    (net (code "42") (name "IO_10") (class "Default")
      (node (ref "R27") (pin "1") (pinfunction "1_1") (pintype "passive"))
      (node (ref "U$1") (pin "10") (pinfunction "10_10") (pintype "bidirectional"))
    )
    (net (code "43") (name "IO_11") (class "Default")
      (node (ref "R22") (pin "1") (pinfunction "1_1") (pintype "passive"))
      (node (ref "U$1") (pin "11") (pinfunction "11_11") (pintype "bidirectional"))
    )
    (net (code "44") (name "IO_12") (class "Default")
      (node (ref "R30") (pin "1") (pinfunction "1_1") (pintype "passive"))
      (node (ref "U$1") (pin "12") (pinfunction "12_12") (pintype "bidirectional"))
    )
    (net (code "45") (name "IO_13") (class "Default")
      (node (ref "R32") (pin "1") (pinfunction "1_1") (pintype "passive"))
      (node (ref "U$1") (pin "13") (pinfunction "13_13") (pintype "bidirectional"))
    )
    (net (code "46") (name "IO_14") (class "Default")
      (node (ref "R33") (pin "1") (pinfunction "1_1") (pintype "passive"))
      (node (ref "U$1") (pin "14") (pinfunction "14_14") (pintype "bidirectional"))
    )
    (net (code "47") (name "IO_15") (class "Default")
      (node (ref "R34") (pin "1") (pinfunction "1_1") (pintype "passive"))
      (node (ref "U$1") (pin "15") (pinfunction "15_15") (pintype "bidirectional"))
    )
    (net (code "48") (name "Net-(CH1.1-Pad3)") (class "Default")
      (node (ref "CH1.1") (pin "3") (pinfunction "3_3") (pintype "passive"))
      (node (ref "CH1.2") (pin "3") (pinfunction "3_3") (pintype "passive"))
      (node (ref "R1") (pin "2") (pinfunction "2_2") (pintype "passive"))
    )
    (net (code "49") (name "Net-(CH2.1-Pad3)") (class "Default")
      (node (ref "CH2.1") (pin "3") (pinfunction "3_3") (pintype "passive"))
      (node (ref "CH2.2") (pin "3") (pinfunction "3_3") (pintype "passive"))
      (node (ref "R2") (pin "2") (pinfunction "2_2") (pintype "passive"))
    )
    (net (code "50") (name "Net-(CH3.1-Pad3)") (class "Default")
      (node (ref "CH3.1") (pin "3") (pinfunction "3_3") (pintype "passive"))
      (node (ref "CH3.2") (pin "3") (pinfunction "3_3") (pintype "passive"))
      (node (ref "R3") (pin "2") (pinfunction "2_2") (pintype "passive"))
    )
    (net (code "51") (name "Net-(CH4.1-Pad3)") (class "Default")
      (node (ref "CH4.1") (pin "3") (pinfunction "3_3") (pintype "passive"))
      (node (ref "CH4.2") (pin "3") (pinfunction "3_3") (pintype "passive"))
      (node (ref "R4") (pin "2") (pinfunction "2_2") (pintype "passive"))
    )
    (net (code "52") (name "Net-(CH5.1-Pad3)") (class "Default")
      (node (ref "CH5.1") (pin "3") (pinfunction "3_3") (pintype "passive"))
      (node (ref "CH5.2") (pin "3") (pinfunction "3_3") (pintype "passive"))
      (node (ref "R5") (pin "2") (pinfunction "2_2") (pintype "passive"))
    )
    (net (code "53") (name "Net-(CH6.1-Pad3)") (class "Default")
      (node (ref "CH6.1") (pin "3") (pinfunction "3_3") (pintype "passive"))
      (node (ref "CH6.2") (pin "3") (pinfunction "3_3") (pintype "passive"))
      (node (ref "R6") (pin "2") (pinfunction "2_2") (pintype "passive"))
    )
    (net (code "54") (name "Net-(CH7.1-Pad3)") (class "Default")
      (node (ref "CH7.1") (pin "3") (pinfunction "3_3") (pintype "passive"))
      (node (ref "CH7.2") (pin "3") (pinfunction "3_3") (pintype "passive"))
      (node (ref "R7") (pin "2") (pinfunction "2_2") (pintype "passive"))
    )
    (net (code "55") (name "Net-(CH8.1-Pad3)") (class "Default")
      (node (ref "CH8.1") (pin "3") (pinfunction "3_3") (pintype "passive"))
      (node (ref "CH8.2") (pin "3") (pinfunction "3_3") (pintype "passive"))
      (node (ref "R8") (pin "2") (pinfunction "2_2") (pintype "passive"))
    )
    (net (code "56") (name "Net-(CH8.3-Pad3)") (class "Default")
      (node (ref "CH8.3") (pin "3") (pinfunction "3_3") (pintype "passive"))
      (node (ref "R41") (pin "2") (pinfunction "2_2") (pintype "passive"))
    )
    (net (code "57") (name "Net-(D1-PadC)") (class "Default")
      (node (ref "D1") (pin "C") (pinfunction "C_C") (pintype "passive"))
      (node (ref "U1") (pin "VIN") (pinfunction "VIN_VIN") (pintype "bidirectional"))
    )
    (net (code "58") (name "Net-(D2-PadA)") (class "Default")
      (node (ref "D2") (pin "A") (pinfunction "A_A") (pintype "passive"))
      (node (ref "MOTOR") (pin "2") (pinfunction "2_2") (pintype "passive"))
      (node (ref "Q11") (pin "D") (pinfunction "D_D") (pintype "passive"))
    )
    (net (code "59") (name "Net-(D3-PadA)") (class "Default")
      (node (ref "D3") (pin "A") (pinfunction "A_A") (pintype "passive"))
      (node (ref "MOTOR1") (pin "2") (pinfunction "2_2") (pintype "passive"))
      (node (ref "Q1") (pin "D") (pinfunction "D_D") (pintype "passive"))
    )
    (net (code "60") (name "Net-(DAC_D-Pad1)") (class "Default")
      (node (ref "DAC_D") (pin "1") (pinfunction "1_1") (pintype "passive"))
      (node (ref "DAC_G") (pin "1") (pinfunction "1_1") (pintype "passive"))
      (node (ref "R13") (pin "1") (pinfunction "1_1") (pintype "passive"))
      (node (ref "R14") (pin "1") (pinfunction "1_1") (pintype "passive"))
      (node (ref "R24") (pin "E") (pinfunction "E_E") (pintype "passive"))
    )
    (net (code "61") (name "Net-(IC1-VI)") (class "Default")
      (node (ref "IC1") (pin "1") (pinfunction "VI_1") (pintype "input"))
      (node (ref "MOTOR2") (pin "2") (pinfunction "2_2") (pintype "passive"))
      (node (ref "X1") (pin "2") (pinfunction "KL_2") (pintype "passive"))
    )
    (net (code "62") (name "Net-(IC2-IN_L)") (class "Default")
      (node (ref "IC2") (pin "3") (pinfunction "IN_R_3") (pintype "input"))
      (node (ref "IC2") (pin "5") (pinfunction "IN_L_5") (pintype "input"))
      (node (ref "R24") (pin "S") (pinfunction "S_S") (pintype "passive"))
    )
    (net (code "63") (name "Net-(OUTPUT1-Pad3)") (class "Default")
      (node (ref "OUTPUT1") (pin "3") (pinfunction "3_3") (pintype "passive"))
      (node (ref "R10") (pin "2") (pinfunction "2_2") (pintype "passive"))
    )
    (net (code "64") (name "Net-(OUTPUT2-Pad3)") (class "Default")
      (node (ref "OUTPUT2") (pin "3") (pinfunction "3_3") (pintype "passive"))
      (node (ref "R11") (pin "2") (pinfunction "2_2") (pintype "passive"))
    )
    (net (code "65") (name "Net-(OUTPUT3-Pad3)") (class "Default")
      (node (ref "OUTPUT3") (pin "3") (pinfunction "3_3") (pintype "passive"))
      (node (ref "R12") (pin "2") (pinfunction "2_2") (pintype "passive"))
    )
    (net (code "66") (name "Net-(OUTPUT4-Pad3)") (class "Default")
      (node (ref "OUTPUT4") (pin "3") (pinfunction "3_3") (pintype "passive"))
      (node (ref "R35") (pin "2") (pinfunction "2_2") (pintype "passive"))
    )
    (net (code "67") (name "Net-(OUTPUT5-Pad3)") (class "Default")
      (node (ref "OUTPUT5") (pin "3") (pinfunction "3_3") (pintype "passive"))
      (node (ref "R36") (pin "2") (pinfunction "2_2") (pintype "passive"))
    )
    (net (code "68") (name "Net-(OUTPUT6-Pad3)") (class "Default")
      (node (ref "OUTPUT6") (pin "3") (pinfunction "3_3") (pintype "passive"))
      (node (ref "R37") (pin "2") (pinfunction "2_2") (pintype "passive"))
    )
    (net (code "69") (name "Net-(OUTPUT7-Pad3)") (class "Default")
      (node (ref "OUTPUT7") (pin "3") (pinfunction "3_3") (pintype "passive"))
      (node (ref "R38") (pin "2") (pinfunction "2_2") (pintype "passive"))
    )
    (net (code "70") (name "Net-(OUTPUT8-Pad3)") (class "Default")
      (node (ref "OUTPUT8") (pin "3") (pinfunction "3_3") (pintype "passive"))
      (node (ref "R39") (pin "2") (pinfunction "2_2") (pintype "passive"))
    )
    (net (code "71") (name "Net-(OUTPUT9-Pad3)") (class "Default")
      (node (ref "OUTPUT9") (pin "3") (pinfunction "3_3") (pintype "passive"))
      (node (ref "R40") (pin "2") (pinfunction "2_2") (pintype "passive"))
    )
    (net (code "72") (name "Net-(Q1-PadG)") (class "Default")
      (node (ref "Q1") (pin "G") (pinfunction "G_G") (pintype "passive"))
      (node (ref "R27") (pin "2") (pinfunction "2_2") (pintype "passive"))
      (node (ref "R28") (pin "2") (pinfunction "2_2") (pintype "passive"))
    )
    (net (code "73") (name "Net-(Q11-PadG)") (class "Default")
      (node (ref "Q11") (pin "G") (pinfunction "G_G") (pintype "passive"))
      (node (ref "R22") (pin "2") (pinfunction "2_2") (pintype "passive"))
      (node (ref "R23") (pin "2") (pinfunction "2_2") (pintype "passive"))
    )
    (net (code "74") (name "Net-(Q13-B)") (class "Default")
      (node (ref "Q13") (pin "2") (pinfunction "B_2") (pintype "passive"))
      (node (ref "R31") (pin "2") (pinfunction "2_2") (pintype "passive"))
    )
    (net (code "75") (name "Net-(QLED1-B)") (class "Default")
      (node (ref "QLED1") (pin "2") (pinfunction "B_2") (pintype "passive"))
      (node (ref "R15") (pin "2") (pinfunction "2_2") (pintype "passive"))
    )
    (net (code "76") (name "Net-(QLED1-C)") (class "Default")
      (node (ref "LED1.1") (pin "2") (pinfunction "2_2") (pintype "passive"))
      (node (ref "LED1.2") (pin "2") (pinfunction "2_2") (pintype "passive"))
      (node (ref "QLED1") (pin "3") (pinfunction "C_3") (pintype "passive"))
    )
    (net (code "77") (name "Net-(QLED2-B)") (class "Default")
      (node (ref "QLED2") (pin "2") (pinfunction "B_2") (pintype "passive"))
      (node (ref "R16") (pin "2") (pinfunction "2_2") (pintype "passive"))
    )
    (net (code "78") (name "Net-(QLED2-C)") (class "Default")
      (node (ref "LED2.1") (pin "2") (pinfunction "2_2") (pintype "passive"))
      (node (ref "LED2.2") (pin "2") (pinfunction "2_2") (pintype "passive"))
      (node (ref "QLED2") (pin "3") (pinfunction "C_3") (pintype "passive"))
    )
    (net (code "79") (name "Net-(QLED3-B)") (class "Default")
      (node (ref "QLED3") (pin "2") (pinfunction "B_2") (pintype "passive"))
      (node (ref "R17") (pin "2") (pinfunction "2_2") (pintype "passive"))
    )
    (net (code "80") (name "Net-(QLED3-C)") (class "Default")
      (node (ref "LED3.1") (pin "2") (pinfunction "2_2") (pintype "passive"))
      (node (ref "LED3.2") (pin "2") (pinfunction "2_2") (pintype "passive"))
      (node (ref "QLED3") (pin "3") (pinfunction "C_3") (pintype "passive"))
    )
    (net (code "81") (name "Net-(QLED4-B)") (class "Default")
      (node (ref "QLED4") (pin "2") (pinfunction "B_2") (pintype "passive"))
      (node (ref "R18") (pin "2") (pinfunction "2_2") (pintype "passive"))
    )
    (net (code "82") (name "Net-(QLED4-C)") (class "Default")
      (node (ref "LED4.1") (pin "2") (pinfunction "2_2") (pintype "passive"))
      (node (ref "LED4.2") (pin "2") (pinfunction "2_2") (pintype "passive"))
      (node (ref "QLED4") (pin "3") (pinfunction "C_3") (pintype "passive"))
    )
    (net (code "83") (name "Net-(QLED5-B)") (class "Default")
      (node (ref "QLED5") (pin "2") (pinfunction "B_2") (pintype "passive"))
      (node (ref "R19") (pin "2") (pinfunction "2_2") (pintype "passive"))
    )
    (net (code "84") (name "Net-(QLED5-C)") (class "Default")
      (node (ref "LED5.1") (pin "2") (pinfunction "2_2") (pintype "passive"))
      (node (ref "LED5.2") (pin "2") (pinfunction "2_2") (pintype "passive"))
      (node (ref "QLED5") (pin "3") (pinfunction "C_3") (pintype "passive"))
    )
    (net (code "85") (name "Net-(QLED6-B)") (class "Default")
      (node (ref "QLED6") (pin "2") (pinfunction "B_2") (pintype "passive"))
      (node (ref "R20") (pin "2") (pinfunction "2_2") (pintype "passive"))
    )
    (net (code "86") (name "Net-(QLED6-C)") (class "Default")
      (node (ref "LED6.1") (pin "2") (pinfunction "2_2") (pintype "passive"))
      (node (ref "LED6.2") (pin "2") (pinfunction "2_2") (pintype "passive"))
      (node (ref "QLED6") (pin "3") (pinfunction "C_3") (pintype "passive"))
    )
    (net (code "87") (name "Net-(QLED7-B)") (class "Default")
      (node (ref "QLED7") (pin "2") (pinfunction "B_2") (pintype "passive"))
      (node (ref "R21") (pin "2") (pinfunction "2_2") (pintype "passive"))
    )
    (net (code "88") (name "Net-(QLED7-C)") (class "Default")
      (node (ref "LED7.1") (pin "2") (pinfunction "2_2") (pintype "passive"))
      (node (ref "LED7.2") (pin "2") (pinfunction "2_2") (pintype "passive"))
      (node (ref "QLED7") (pin "3") (pinfunction "C_3") (pintype "passive"))
    )
    (net (code "89") (name "Net-(QLED8-B)") (class "Default")
      (node (ref "QLED8") (pin "2") (pinfunction "B_2") (pintype "passive"))
      (node (ref "R9") (pin "2") (pinfunction "2_2") (pintype "passive"))
    )
    (net (code "90") (name "Net-(QLED8-C)") (class "Default")
      (node (ref "LED7.3") (pin "2") (pinfunction "2_2") (pintype "passive"))
      (node (ref "LED7.4") (pin "2") (pinfunction "2_2") (pintype "passive"))
      (node (ref "QLED8") (pin "3") (pinfunction "C_3") (pintype "passive"))
    )
    (net (code "91") (name "Net-(QLED9-B)") (class "Default")
      (node (ref "QLED9") (pin "2") (pinfunction "B_2") (pintype "passive"))
      (node (ref "R25") (pin "2") (pinfunction "2_2") (pintype "passive"))
    )
    (net (code "92") (name "Net-(QLED9-C)") (class "Default")
      (node (ref "LED7.5") (pin "2") (pinfunction "2_2") (pintype "passive"))
      (node (ref "LED7.6") (pin "2") (pinfunction "2_2") (pintype "passive"))
      (node (ref "QLED9") (pin "3") (pinfunction "C_3") (pintype "passive"))
    )
    (net (code "93") (name "Net-(QLED10-B)") (class "Default")
      (node (ref "QLED10") (pin "2") (pinfunction "B_2") (pintype "passive"))
      (node (ref "R26") (pin "2") (pinfunction "2_2") (pintype "passive"))
    )
    (net (code "94") (name "Net-(QLED10-C)") (class "Default")
      (node (ref "LED7.7") (pin "2") (pinfunction "2_2") (pintype "passive"))
      (node (ref "LED7.8") (pin "2") (pinfunction "2_2") (pintype "passive"))
      (node (ref "QLED10") (pin "3") (pinfunction "C_3") (pintype "passive"))
    )
    (net (code "95") (name "Net-(QLED13-B)") (class "Default")
      (node (ref "QLED13") (pin "2") (pinfunction "B_2") (pintype "passive"))
      (node (ref "R30") (pin "2") (pinfunction "2_2") (pintype "passive"))
    )
    (net (code "96") (name "Net-(QLED13-C)") (class "Default")
      (node (ref "LED7.13") (pin "2") (pinfunction "2_2") (pintype "passive"))
      (node (ref "LED7.14") (pin "2") (pinfunction "2_2") (pintype "passive"))
      (node (ref "QLED13") (pin "3") (pinfunction "C_3") (pintype "passive"))
    )
    (net (code "97") (name "Net-(QLED14-B)") (class "Default")
      (node (ref "QLED14") (pin "2") (pinfunction "B_2") (pintype "passive"))
      (node (ref "R32") (pin "2") (pinfunction "2_2") (pintype "passive"))
    )
    (net (code "98") (name "Net-(QLED14-C)") (class "Default")
      (node (ref "LED7.15") (pin "2") (pinfunction "2_2") (pintype "passive"))
      (node (ref "LED7.16") (pin "2") (pinfunction "2_2") (pintype "passive"))
      (node (ref "QLED14") (pin "3") (pinfunction "C_3") (pintype "passive"))
    )
    (net (code "99") (name "Net-(QLED15-B)") (class "Default")
      (node (ref "QLED15") (pin "2") (pinfunction "B_2") (pintype "passive"))
      (node (ref "R33") (pin "2") (pinfunction "2_2") (pintype "passive"))
    )
    (net (code "100") (name "Net-(QLED15-C)") (class "Default")
      (node (ref "LED7.17") (pin "2") (pinfunction "2_2") (pintype "passive"))
      (node (ref "LED7.18") (pin "2") (pinfunction "2_2") (pintype "passive"))
      (node (ref "QLED15") (pin "3") (pinfunction "C_3") (pintype "passive"))
    )
    (net (code "101") (name "Net-(QLED16-B)") (class "Default")
      (node (ref "QLED16") (pin "2") (pinfunction "B_2") (pintype "passive"))
      (node (ref "R34") (pin "2") (pinfunction "2_2") (pintype "passive"))
    )
    (net (code "102") (name "Net-(QLED16-C)") (class "Default")
      (node (ref "LED7.19") (pin "2") (pinfunction "2_2") (pintype "passive"))
      (node (ref "LED7.20") (pin "2") (pinfunction "2_2") (pintype "passive"))
      (node (ref "QLED16") (pin "3") (pinfunction "C_3") (pintype "passive"))
    )
    (net (code "103") (name "unconnected-(IC2-L+-Pad7)") (class "Default")
      (node (ref "IC2") (pin "7") (pinfunction "L+_7") (pintype "output"))
    )
    (net (code "104") (name "unconnected-(IC2-L--Pad6)") (class "Default")
      (node (ref "IC2") (pin "6") (pinfunction "L-_6") (pintype "output"))
    )
    (net (code "105") (name "unconnected-(IC2-R+-Pad8)") (class "Default")
      (node (ref "IC2") (pin "8") (pinfunction "R+_8") (pintype "output"))
    )
    (net (code "106") (name "unconnected-(IC2-R--Pad9)") (class "Default")
      (node (ref "IC2") (pin "9") (pinfunction "R-_9") (pintype "output"))
    )
    (net (code "107") (name "unconnected-(U$1-Pad3.3V_)") (class "Default")
      (node (ref "U$1") (pin "3.3V_") (pinfunction "3.3V__3.3V_") (pintype "bidirectional"))
    )
    (net (code "108") (name "unconnected-(U$1-PadGND_)") (class "Default")
      (node (ref "U$1") (pin "GND_") (pinfunction "GND__GND_") (pintype "bidirectional"))
    )
    (net (code "109") (name "unconnected-(U$1-PadINT)") (class "Default")
      (node (ref "U$1") (pin "INT") (pinfunction "INT_INT") (pintype "bidirectional"))
    )
    (net (code "110") (name "unconnected-(U$1-PadOSCIO)") (class "Default")
      (node (ref "U$1") (pin "OSCIO") (pinfunction "OSCIO_OSCIO") (pintype "bidirectional"))
    )
    (net (code "111") (name "unconnected-(U$1-PadRST)") (class "Default")
      (node (ref "U$1") (pin "RST") (pinfunction "RST_RST") (pintype "bidirectional"))
    )
    (net (code "112") (name "unconnected-(U$1-PadVCC1)") (class "Default")
      (node (ref "U$1") (pin "VCC1") (pinfunction "VCC1_VCC1") (pintype "bidirectional"))
    )
    (net (code "113") (name "unconnected-(U$1-PadVCC2)") (class "Default")
      (node (ref "U$1") (pin "VCC2") (pinfunction "VCC2_VCC2") (pintype "bidirectional"))
    )
    (net (code "114") (name "unconnected-(U$1-Pad_3.3V)") (class "Default")
      (node (ref "U$1") (pin "_3.3V") (pinfunction "_3.3V__3.3V") (pintype "bidirectional"))
    )
    (net (code "115") (name "unconnected-(U$1-Pad_GND)") (class "Default")
      (node (ref "U$1") (pin "_GND") (pinfunction "_GND__GND") (pintype "bidirectional"))
    )
    (net (code "116") (name "unconnected-(U1-PadEN)") (class "Default")
      (node (ref "U1") (pin "EN") (pinfunction "EN_EN") (pintype "bidirectional"))
    )
  )
)
